# V4_0.net
KiCad netlist of a schematic drawn in Altium Designer
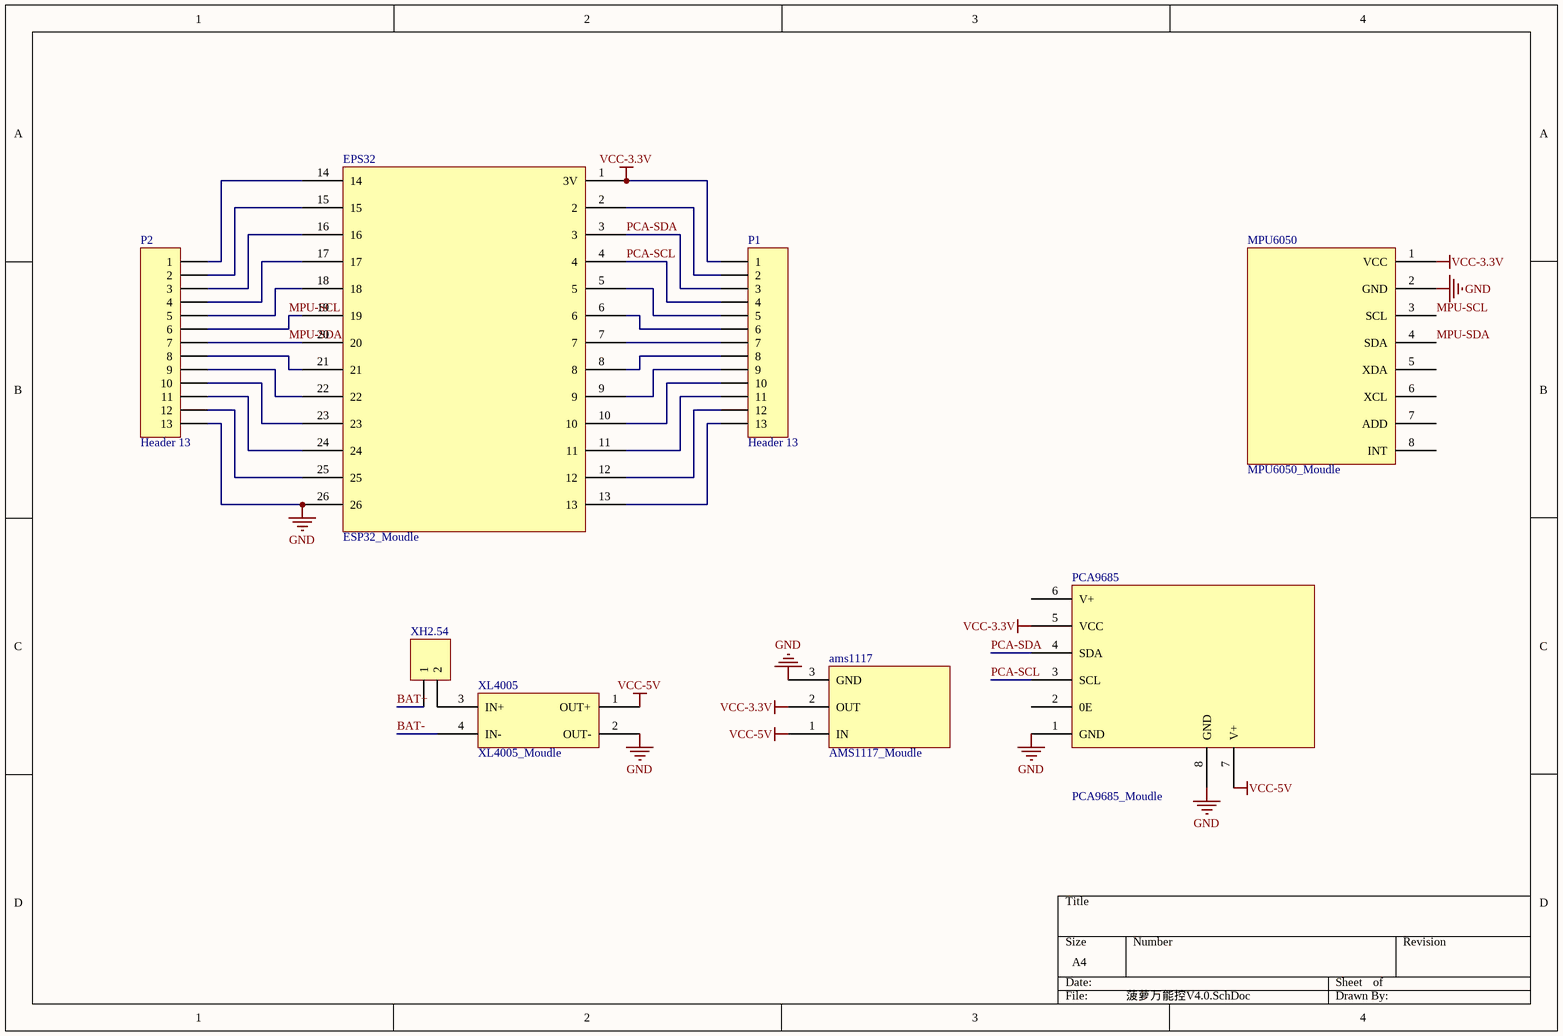
[diagram p0: 菠萝万能控V4.0.SchDoc]

(export (version "E")
  (design (tool "Eeschema 10.0.6"))
  (components
    (comp (ref "ams1117")
      (value "AMS1117_Moudle")
      (footprint "AMS1117_Moudle")
      (libsource (lib "PADog") (part "AMS1117_Moudle"))
    )
    (comp (ref "EPS32")
      (value "ESP32_Moudle")
      (footprint "ESP32_Moudle")
      (libsource (lib "PADog") (part "ESP32_Moudle"))
    )
    (comp (ref "MPU6050")
      (value "MPU6050_Moudle")
      (footprint "MPU6050_Moudle")
      (libsource (lib "PADog") (part "MPU6050_Moudle"))
    )
    (comp (ref "P1")
      (value "Header 13")
      (footprint "HDR1X13")
      (description "Header, 13-Pin")
      (fields (field (name "PUBLISHER") "Altium Limited"))
      (libsource (lib "") (part "Header 13_1"))
    )
    (comp (ref "P2")
      (value "Header 13")
      (footprint "HDR1X13")
      (description "Header, 13-Pin")
      (fields (field (name "PUBLISHER") "Altium Limited"))
      (libsource (lib "Miscellaneous Connectors") (part "Header 13"))
    )
    (comp (ref "PCA9685")
      (value "PCA9685_Moudle")
      (footprint "PCA9685_Moudle")
      (libsource (lib "PADog") (part "PCA9685_Moudle"))
    )
    (comp (ref "XH2.54")
      (value "Header 2")
      (footprint "HDR1X2")
      (description "Header, 2-Pin")
      (fields (field (name "PUBLISHER") "Altium Limited"))
      (libsource (lib "Miscellaneous Connectors") (part "Header 2"))
    )
    (comp (ref "XL4005")
      (value "XL4005_Moudle")
      (footprint "XL4005_Moudle")
      (libsource (lib "PADog") (part "XL4005_Moudle"))
    )
  )
  (nets
    (net (code "1") (name "/BAT+") (class "Default")
      (node (ref "XH2.54") (pin "1") (pinfunction "1_1") (pintype "passive"))
    )
    (net (code "2") (name "/BAT-") (class "Default")
      (node (ref "XL4005") (pin "4") (pinfunction "IN-_4") (pintype "passive"))
    )
    (net (code "3") (name "/MPU-SCL") (class "Default")
      (node (ref "EPS32") (pin "19") (pinfunction "19_19") (pintype "passive"))
      (node (ref "MPU6050") (pin "3") (pinfunction "SCL_3") (pintype "passive"))
      (node (ref "P2") (pin "6") (pinfunction "6_6") (pintype "passive"))
    )
    (net (code "4") (name "/MPU-SDA") (class "Default")
      (node (ref "EPS32") (pin "20") (pinfunction "20_20") (pintype "passive"))
      (node (ref "MPU6050") (pin "4") (pinfunction "SDA_4") (pintype "passive"))
      (node (ref "P2") (pin "7") (pinfunction "7_7") (pintype "passive"))
    )
    (net (code "5") (name "/PCA-SCL") (class "Default")
      (node (ref "EPS32") (pin "4") (pinfunction "4_4") (pintype "passive"))
      (node (ref "P1") (pin "4") (pinfunction "4_4") (pintype "passive"))
      (node (ref "PCA9685") (pin "3") (pinfunction "SCL_3") (pintype "passive"))
    )
    (net (code "6") (name "/PCA-SDA") (class "Default")
      (node (ref "EPS32") (pin "3") (pinfunction "3_3") (pintype "passive"))
      (node (ref "P1") (pin "3") (pinfunction "3_3") (pintype "passive"))
      (node (ref "PCA9685") (pin "4") (pinfunction "SDA_4") (pintype "passive"))
    )
    (net (code "7") (name "GND") (class "Default")
      (node (ref "EPS32") (pin "26") (pinfunction "26_26") (pintype "passive"))
      (node (ref "MPU6050") (pin "2") (pinfunction "GND_2") (pintype "passive"))
      (node (ref "P2") (pin "13") (pinfunction "13_13") (pintype "passive"))
      (node (ref "PCA9685") (pin "1") (pinfunction "GND_1") (pintype "passive"))
      (node (ref "PCA9685") (pin "8") (pinfunction "GND_8") (pintype "passive"))
      (node (ref "XL4005") (pin "2") (pinfunction "OUT-_2") (pintype "passive"))
      (node (ref "ams1117") (pin "3") (pinfunction "GND_3") (pintype "passive"))
    )
    (net (code "8") (name "Net-(EPS32-Pad2)") (class "Default")
      (node (ref "EPS32") (pin "2") (pinfunction "2_2") (pintype "passive"))
      (node (ref "P1") (pin "2") (pinfunction "2_2") (pintype "passive"))
    )
    (net (code "9") (name "Net-(EPS32-Pad5)") (class "Default")
      (node (ref "EPS32") (pin "5") (pinfunction "5_5") (pintype "passive"))
      (node (ref "P1") (pin "5") (pinfunction "5_5") (pintype "passive"))
    )
    (net (code "10") (name "Net-(EPS32-Pad6)") (class "Default")
      (node (ref "EPS32") (pin "6") (pinfunction "6_6") (pintype "passive"))
      (node (ref "P1") (pin "6") (pinfunction "6_6") (pintype "passive"))
    )
    (net (code "11") (name "Net-(EPS32-Pad7)") (class "Default")
      (node (ref "EPS32") (pin "7") (pinfunction "7_7") (pintype "passive"))
      (node (ref "P1") (pin "7") (pinfunction "7_7") (pintype "passive"))
    )
    (net (code "12") (name "Net-(EPS32-Pad8)") (class "Default")
      (node (ref "EPS32") (pin "8") (pinfunction "8_8") (pintype "passive"))
      (node (ref "P1") (pin "8") (pinfunction "8_8") (pintype "passive"))
    )
    (net (code "13") (name "Net-(EPS32-Pad9)") (class "Default")
      (node (ref "EPS32") (pin "9") (pinfunction "9_9") (pintype "passive"))
      (node (ref "P1") (pin "9") (pinfunction "9_9") (pintype "passive"))
    )
    (net (code "14") (name "Net-(EPS32-Pad10)") (class "Default")
      (node (ref "EPS32") (pin "10") (pinfunction "10_10") (pintype "passive"))
      (node (ref "P1") (pin "10") (pinfunction "10_10") (pintype "passive"))
    )
    (net (code "15") (name "Net-(EPS32-Pad11)") (class "Default")
      (node (ref "EPS32") (pin "11") (pinfunction "11_11") (pintype "passive"))
      (node (ref "P1") (pin "11") (pinfunction "11_11") (pintype "passive"))
    )
    (net (code "16") (name "Net-(EPS32-Pad12)") (class "Default")
      (node (ref "EPS32") (pin "12") (pinfunction "12_12") (pintype "passive"))
      (node (ref "P1") (pin "12") (pinfunction "12_12") (pintype "passive"))
    )
    (net (code "17") (name "Net-(EPS32-Pad13)") (class "Default")
      (node (ref "EPS32") (pin "13") (pinfunction "13_13") (pintype "passive"))
      (node (ref "P1") (pin "13") (pinfunction "13_13") (pintype "passive"))
    )
    (net (code "18") (name "Net-(EPS32-Pad14)") (class "Default")
      (node (ref "EPS32") (pin "14") (pinfunction "14_14") (pintype "passive"))
      (node (ref "P2") (pin "1") (pinfunction "1_1") (pintype "passive"))
    )
    (net (code "19") (name "Net-(EPS32-Pad15)") (class "Default")
      (node (ref "EPS32") (pin "15") (pinfunction "15_15") (pintype "passive"))
      (node (ref "P2") (pin "2") (pinfunction "2_2") (pintype "passive"))
    )
    (net (code "20") (name "Net-(EPS32-Pad16)") (class "Default")
      (node (ref "EPS32") (pin "16") (pinfunction "16_16") (pintype "passive"))
      (node (ref "P2") (pin "3") (pinfunction "3_3") (pintype "passive"))
    )
    (net (code "21") (name "Net-(EPS32-Pad17)") (class "Default")
      (node (ref "EPS32") (pin "17") (pinfunction "17_17") (pintype "passive"))
      (node (ref "P2") (pin "4") (pinfunction "4_4") (pintype "passive"))
    )
    (net (code "22") (name "Net-(EPS32-Pad18)") (class "Default")
      (node (ref "EPS32") (pin "18") (pinfunction "18_18") (pintype "passive"))
      (node (ref "P2") (pin "5") (pinfunction "5_5") (pintype "passive"))
    )
    (net (code "23") (name "Net-(EPS32-Pad21)") (class "Default")
      (node (ref "EPS32") (pin "21") (pinfunction "21_21") (pintype "passive"))
      (node (ref "P2") (pin "8") (pinfunction "8_8") (pintype "passive"))
    )
    (net (code "24") (name "Net-(EPS32-Pad22)") (class "Default")
      (node (ref "EPS32") (pin "22") (pinfunction "22_22") (pintype "passive"))
      (node (ref "P2") (pin "9") (pinfunction "9_9") (pintype "passive"))
    )
    (net (code "25") (name "Net-(EPS32-Pad23)") (class "Default")
      (node (ref "EPS32") (pin "23") (pinfunction "23_23") (pintype "passive"))
      (node (ref "P2") (pin "10") (pinfunction "10_10") (pintype "passive"))
    )
    (net (code "26") (name "Net-(EPS32-Pad24)") (class "Default")
      (node (ref "EPS32") (pin "24") (pinfunction "24_24") (pintype "passive"))
      (node (ref "P2") (pin "11") (pinfunction "11_11") (pintype "passive"))
    )
    (net (code "27") (name "Net-(EPS32-Pad25)") (class "Default")
      (node (ref "EPS32") (pin "25") (pinfunction "25_25") (pintype "passive"))
      (node (ref "P2") (pin "12") (pinfunction "12_12") (pintype "passive"))
    )
    (net (code "28") (name "Net-(XL4005-IN+)") (class "Default")
      (node (ref "XH2.54") (pin "2") (pinfunction "2_2") (pintype "passive"))
      (node (ref "XL4005") (pin "3") (pinfunction "IN+_3") (pintype "passive"))
    )
    (net (code "29") (name "VCC-3.3V") (class "Default")
      (node (ref "EPS32") (pin "1") (pinfunction "3V_1") (pintype "passive"))
      (node (ref "MPU6050") (pin "1") (pinfunction "VCC_1") (pintype "passive"))
      (node (ref "P1") (pin "1") (pinfunction "1_1") (pintype "passive"))
      (node (ref "PCA9685") (pin "5") (pinfunction "VCC_5") (pintype "passive"))
      (node (ref "ams1117") (pin "2") (pinfunction "OUT_2") (pintype "passive"))
    )
    (net (code "30") (name "VCC-5V") (class "Default")
      (node (ref "PCA9685") (pin "7") (pinfunction "V+_7") (pintype "passive"))
      (node (ref "XL4005") (pin "1") (pinfunction "OUT+_1") (pintype "passive"))
      (node (ref "ams1117") (pin "1") (pinfunction "IN_1") (pintype "passive"))
    )
    (net (code "31") (name "unconnected-(MPU6050-ADD-Pad7)") (class "Default")
      (node (ref "MPU6050") (pin "7") (pinfunction "ADD_7") (pintype "passive"))
    )
    (net (code "32") (name "unconnected-(MPU6050-INT-Pad8)") (class "Default")
      (node (ref "MPU6050") (pin "8") (pinfunction "INT_8") (pintype "passive"))
    )
    (net (code "33") (name "unconnected-(MPU6050-XCL-Pad6)") (class "Default")
      (node (ref "MPU6050") (pin "6") (pinfunction "XCL_6") (pintype "passive"))
    )
    (net (code "34") (name "unconnected-(MPU6050-XDA-Pad5)") (class "Default")
      (node (ref "MPU6050") (pin "5") (pinfunction "XDA_5") (pintype "passive"))
    )
    (net (code "35") (name "unconnected-(PCA9685-0E-Pad2)") (class "Default")
      (node (ref "PCA9685") (pin "2") (pinfunction "0E_2") (pintype "passive"))
    )
    (net (code "36") (name "unconnected-(PCA9685-V+-Pad6)") (class "Default")
      (node (ref "PCA9685") (pin "6") (pinfunction "V+_6") (pintype "passive"))
    )
  )
)
